# Connectors.net
KiCad netlist of a schematic drawn in Altium Designer
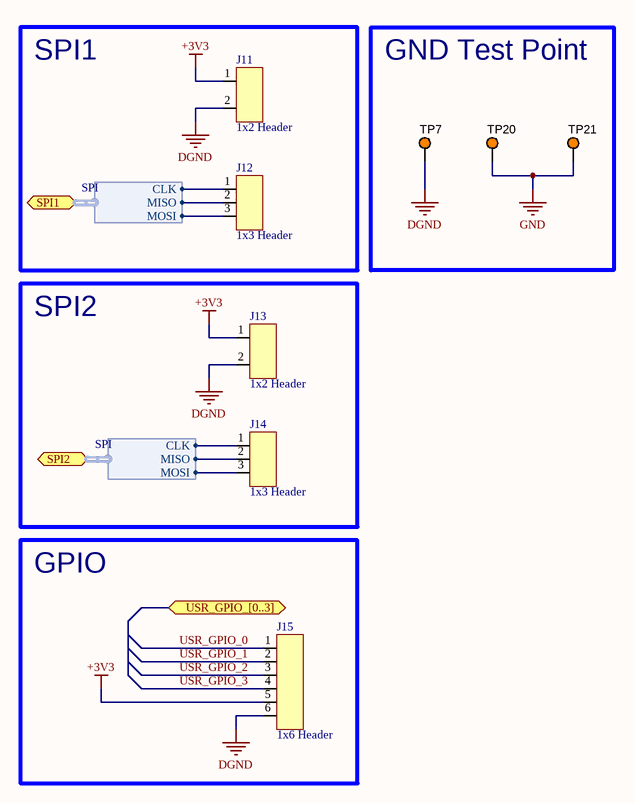
[diagram p0: Connectors.SchDoc]

(export (version "E")
  (design (tool "Eeschema 10.0.6"))
  (components
    (comp (ref "J11")
      (value "1x2 Header")
      (footprint "1x2 Header-Footprint-1")
      (libsource (lib "Leonhard Waibl") (part "1x2 Header-Symbol-1"))
    )
    (comp (ref "J12")
      (value "1x3 Header")
      (footprint "1x4 Header-Footprint-1")
      (libsource (lib "Leonhard Waibl") (part "1x3 Header"))
    )
    (comp (ref "J13")
      (value "1x2 Header")
      (footprint "1x2 Header-Footprint-1")
      (libsource (lib "Leonhard Waibl") (part "1x2 Header-Symbol-1"))
    )
    (comp (ref "J14")
      (value "1x3 Header")
      (footprint "1x4 Header-Footprint-1")
      (libsource (lib "Leonhard Waibl") (part "1x3 Header"))
    )
    (comp (ref "J15")
      (value "1x6 Header")
      (footprint "1x6 Header-Footprint-1")
      (libsource (lib "Leonhard Waibl") (part "1x6 Header-Symbol-1"))
    )
    (comp (ref "TP7")
      (value "5003")
      (footprint "KSTN-5003")
      (description "Test Point, Orange, Height 4.6 mm, Tail Length 3 mm, 1-Pin THD, RoHS")
      (fields (field (name "MANUFACTURER") "Keystone"))
      (libsource (lib "Leonhard Waibl") (part "TESTPOINT_ORANGE"))
    )
    (comp (ref "TP20")
      (value "5003")
      (footprint "KSTN-5003")
      (description "Test Point, Orange, Height 4.6 mm, Tail Length 3 mm, 1-Pin THD, RoHS")
      (fields (field (name "MANUFACTURER") "Keystone"))
      (libsource (lib "Leonhard Waibl") (part "TESTPOINT_ORANGE"))
    )
    (comp (ref "TP21")
      (value "5003")
      (footprint "KSTN-5003")
      (description "Test Point, Orange, Height 4.6 mm, Tail Length 3 mm, 1-Pin THD, RoHS")
      (fields (field (name "MANUFACTURER") "Keystone"))
      (libsource (lib "Leonhard Waibl") (part "TESTPOINT_ORANGE"))
    )
  )
  (nets
    (net (code "2") (name "+3V3") (class "Default")
      (node (ref "J11") (pin "1") (pinfunction "1_1") (pintype "passive"))
      (node (ref "J13") (pin "1") (pinfunction "1_1") (pintype "passive"))
      (node (ref "J15") (pin "5") (pinfunction "5_5") (pintype "passive"))
    )
    (net (code "3") (name "/USR_GPIO_0") (class "Default")
      (node (ref "J15") (pin "1") (pinfunction "1_1") (pintype "passive"))
    )
    (net (code "4") (name "/USR_GPIO_1") (class "Default")
      (node (ref "J15") (pin "2") (pinfunction "2_2") (pintype "passive"))
    )
    (net (code "5") (name "/USR_GPIO_2") (class "Default")
      (node (ref "J15") (pin "3") (pinfunction "3_3") (pintype "passive"))
    )
    (net (code "6") (name "/USR_GPIO_3") (class "Default")
      (node (ref "J15") (pin "4") (pinfunction "4_4") (pintype "passive"))
    )
    (net (code "9") (name "DGND") (class "Default")
      (node (ref "J11") (pin "2") (pinfunction "2_2") (pintype "passive"))
      (node (ref "J13") (pin "2") (pinfunction "2_2") (pintype "passive"))
      (node (ref "J15") (pin "6") (pinfunction "6_6") (pintype "passive"))
      (node (ref "TP7") (pin "1") (pinfunction "1_1") (pintype "passive"))
    )
    (net (code "10") (name "GND") (class "Default")
      (node (ref "TP20") (pin "1") (pinfunction "1_1") (pintype "passive"))
      (node (ref "TP21") (pin "1") (pinfunction "1_1") (pintype "passive"))
    )
    (net (code "11") (name "unconnected-(J12-Pad1)") (class "Default")
      (node (ref "J12") (pin "1") (pinfunction "1_1") (pintype "passive"))
    )
    (net (code "12") (name "unconnected-(J12-Pad2)") (class "Default")
      (node (ref "J12") (pin "2") (pinfunction "2_2") (pintype "passive"))
    )
    (net (code "13") (name "unconnected-(J12-Pad3)") (class "Default")
      (node (ref "J12") (pin "3") (pinfunction "3_3") (pintype "passive"))
    )
    (net (code "14") (name "unconnected-(J14-Pad1)") (class "Default")
      (node (ref "J14") (pin "1") (pinfunction "1_1") (pintype "passive"))
    )
    (net (code "15") (name "unconnected-(J14-Pad2)") (class "Default")
      (node (ref "J14") (pin "2") (pinfunction "2_2") (pintype "passive"))
    )
    (net (code "16") (name "unconnected-(J14-Pad3)") (class "Default")
      (node (ref "J14") (pin "3") (pinfunction "3_3") (pintype "passive"))
    )
  )
)
